# LPF_PA.net
KiCad netlist of a schematic drawn in Altium Designer
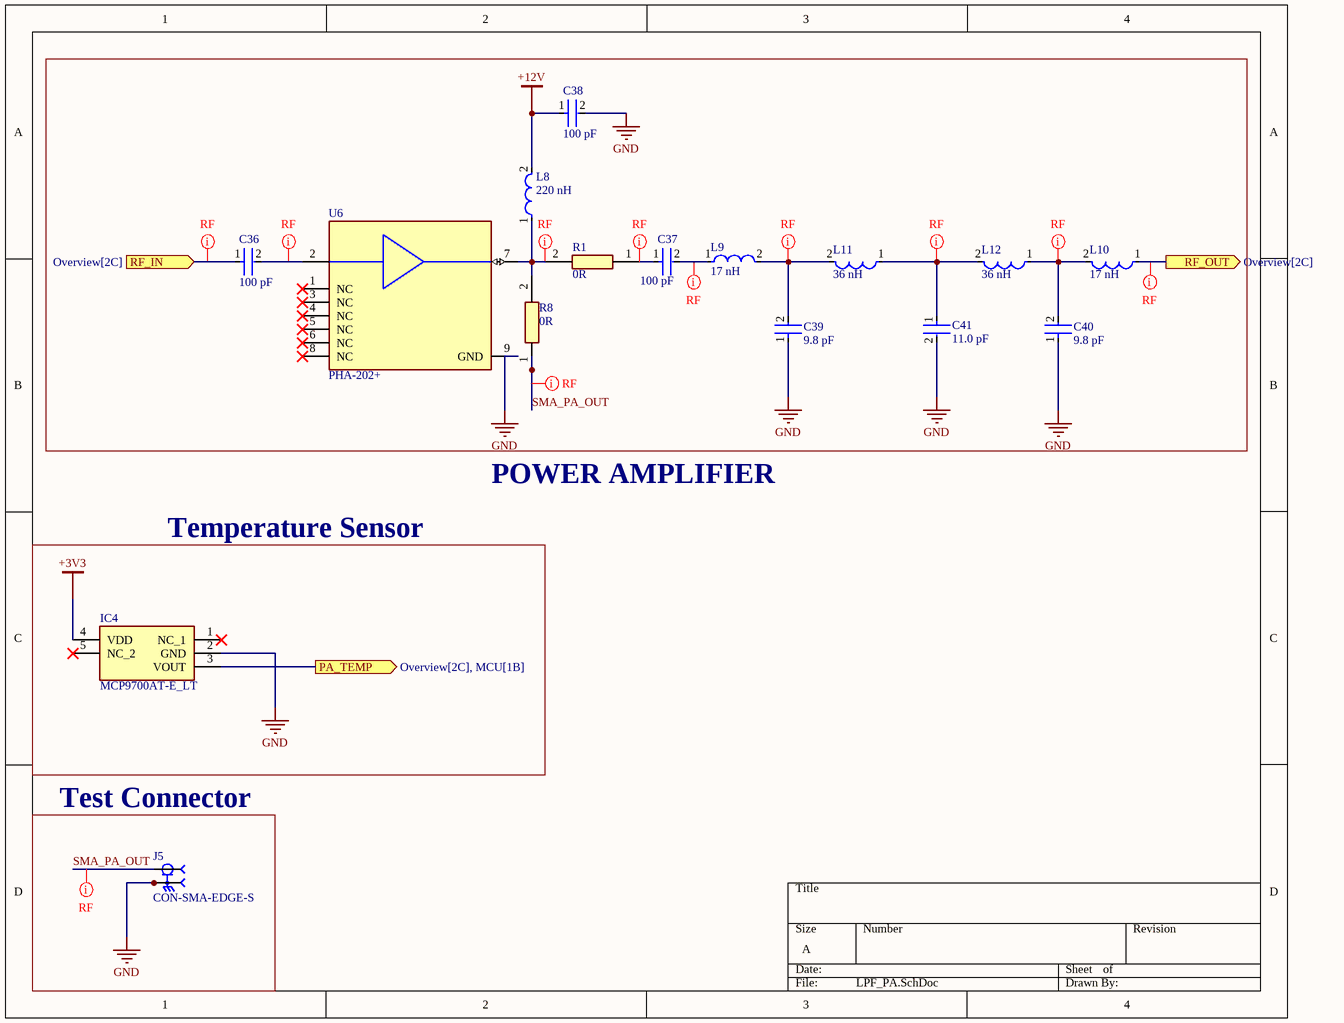
[diagram p0: LPF_PA.SchDoc]

(export (version "E")
  (design (tool "Eeschema 10.0.6"))
  (components
    (comp (ref "C36")
      (value "100 pF")
      (footprint "FP-GQM187-0_15-MFG")
      (description "Ceramic Capacitor 100pF ±5% 250VDC C0G 0603 Paper T/R Name: GQM1875C2E101JB12D")
      (fields (field (name "TOLERANCE") "5%"))
      (libsource (lib "Altium Content Vault") (part "02cd4be3c70576c341d710602a673aa"))
    )
    (comp (ref "C37")
      (value "100 pF")
      (footprint "FP-GQM187-0_15-MFG")
      (description "Ceramic Capacitor 100pF ±5% 250VDC C0G 0603 Paper T/R Name: GQM1875C2E101JB12D")
      (fields (field (name "TOLERANCE") "5%"))
      (libsource (lib "Altium Content Vault") (part "02cd4be3c70576c341d710602a673aa"))
    )
    (comp (ref "C38")
      (value "100 pF")
      (footprint "FP-GQM187-0_15-MFG")
      (description "Ceramic Capacitor 100pF ±5% 250VDC C0G 0603 Paper T/R Name: GQM1875C2E101JB12D")
      (fields (field (name "TOLERANCE") "5%"))
      (libsource (lib "Altium Content Vault") (part "02cd4be3c70576c341d710602a673aa"))
    )
    (comp (ref "C39")
      (value "9.8 pF")
      (footprint "FP-GJM155-0_05-IPC_A")
      (description "Multi-Layer Ceramic Capacitor 9.8pF C0G  ±0.05pF 0402 Paper T/R Name: GJM1555C1H9R8WB01D")
      (libsource (lib "Altium Content Vault") (part "02cd4be3c70576c341d710602a673aa"))
    )
    (comp (ref "C40")
      (value "9.8 pF")
      (footprint "FP-GJM155-0_05-IPC_A")
      (description "Multi-Layer Ceramic Capacitor 9.8pF C0G  ±0.05pF 0402 Paper T/R Name: GJM1555C1H9R8WB01D")
      (libsource (lib "Altium Content Vault") (part "02cd4be3c70576c341d710602a673aa"))
    )
    (comp (ref "C41")
      (value "11.0 pF")
      (footprint "FP-GJM155-0_05-IPC_B")
      (description "Multi-Layer Ceramic Capacitor 11pF C0G  ±2% 0402 Paper T/R Name: GJM1555C1H110GB01D")
      (fields (field (name "TOLERANCE") "2%"))
      (libsource (lib "Altium Content Vault") (part "02cd4be3c70576c341d710602a673aa"))
    )
    (comp (ref "IC4")
      (value "MCP9700AT-E_LT")
      (footprint "SamacSys:SOT65P210X110-5N")
      (description "Integrated Circuit")
      (fields
        (field (name "MANUFACTURER_PART_NUMBER") "MCP9700AT-E/LT")
        (field (name "MOUSER PART NUMBER") "579-MCP9700AT-E/LT")
      )
      (libsource (lib "*") (part "MCP9700AT-E_LT"))
    )
    (comp (ref "J5")
      (value "CON-SMA-EDGE-S")
      (footprint "RFSOLUTIONS_CON-SMA-EDGE-S")
      (description "SMA Connector Jack, Female Socket - Board Edge, End Launch Solder")
      (fields (field (name "MF") "RF Solutions") (field (name "DIGI-KEY_PART_NUMBER") "CON-SMA-EDGE-S-ND"))
      (libsource (lib "Americas- Calgary to Space- Calgary University") (part "CON-SMA-EDGE-S"))
    )
    (comp (ref "L8")
      (value "220 nH")
      (footprint "FP-LQW18AN_80-MFG")
      (description "Wire Wound RF Inductor for Automotive 220nH ±5% 280mA 2.08Ω 0603 (1608) Name: LQW18ANR22J8ZD")
      (libsource (lib "Altium Content Vault") (part "725321dda6339637d4d059423bc1c3c"))
    )
    (comp (ref "L9")
      (value "17 nH")
      (footprint "FP-LQW18AN_80-MFG")
      (description "Wire Wound RF Inductor for Automotive 17nH ±2% 1400mA 0.075Ω 0603 (1608) Name: LQW18AN17NG8ZD")
      (libsource (lib "Altium Content Vault") (part "725321dda6339637d4d059423bc1c3c"))
    )
    (comp (ref "L10")
      (value "17 nH")
      (footprint "FP-LQW18AN_80-MFG")
      (description "Wire Wound RF Inductor for Automotive 17nH ±2% 1400mA 0.075Ω 0603 (1608) Name: LQW18AN17NG8ZD")
      (libsource (lib "Altium Content Vault") (part "725321dda6339637d4d059423bc1c3c"))
    )
    (comp (ref "L11")
      (value "36 nH")
      (footprint "FP-LQW18AN_80-MFG")
      (description "Wire Wound RF Inductor for Automotive 36nH ±5% 910mA 0.2Ω 0603 (1608) Name: LQW18AN36NJ8ZD")
      (libsource (lib "Altium Content Vault") (part "725321dda6339637d4d059423bc1c3c"))
    )
    (comp (ref "L12")
      (value "36 nH")
      (footprint "FP-LQW18AN_80-MFG")
      (description "Wire Wound RF Inductor for Automotive 36nH ±5% 910mA 0.2Ω 0603 (1608) Name: LQW18AN36NJ8ZD")
      (libsource (lib "Altium Content Vault") (part "725321dda6339637d4d059423bc1c3c"))
    )
    (comp (ref "R1")
      (value "0R")
      (footprint "SamacSys:RESC1608X55N")
      (description "RC0603JR-070RL")
      (fields (field (name "MOUSER PART NUMBER") "603-RC0603JR-070RL"))
      (libsource (lib "") (part "RC0603JR-070RL_1"))
    )
    (comp (ref "R8")
      (value "0R")
      (footprint "SamacSys:RESC1608X55N")
      (description "RC0603JR-070RL")
      (fields (field (name "MOUSER PART NUMBER") "603-RC0603JR-070RL"))
      (libsource (lib "*") (part "RC0603JR-070RL"))
    )
    (comp (ref "U6")
      (value "PHA-202+")
      (footprint "FP-DL1636-MFG")
      (description "Ultra High Dynamic Range Monolithic Amplifier")
      (fields
        (field (name "MANUFACTURER") "Mini-Circuits")
        (field (name "OCTOPART") "https://octopart.com/pha-202%2B-mini-circuits-107467474")
      )
      (libsource (lib "Altium Content Vault") (part "dc888fa33c990a84ca3dff72230b88d"))
    )
  )
  (nets
    (net (code "1") (name "+3V3") (class "Default")
      (node (ref "IC4") (pin "4") (pinfunction "VDD_4") (pintype "passive"))
    )
    (net (code "2") (name "+12V") (class "Default")
      (node (ref "C38") (pin "1") (pinfunction "1_1") (pintype "passive"))
      (node (ref "L8") (pin "2") (pinfunction "2_2") (pintype "passive"))
    )
    (net (code "3") (name "/PA_TEMP") (class "Default")
      (node (ref "IC4") (pin "3") (pinfunction "VOUT_3") (pintype "passive"))
    )
    (net (code "4") (name "/RF_IN") (class "Default")
      (node (ref "C36") (pin "1") (pinfunction "1_1") (pintype "passive"))
    )
    (net (code "5") (name "/RF_OUT") (class "Default")
      (node (ref "L10") (pin "1") (pinfunction "1_1") (pintype "passive"))
    )
    (net (code "6") (name "/SMA_PA_OUT") (class "Default")
      (node (ref "J5") (pin "1") (pinfunction "1_1") (pintype "passive"))
      (node (ref "R8") (pin "1") (pinfunction "1_1") (pintype "passive"))
    )
    (net (code "7") (name "GND") (class "Default")
      (node (ref "C38") (pin "2") (pinfunction "2_2") (pintype "passive"))
      (node (ref "C39") (pin "1") (pinfunction "1_1") (pintype "passive"))
      (node (ref "C40") (pin "1") (pinfunction "1_1") (pintype "passive"))
      (node (ref "C41") (pin "2") (pinfunction "2_2") (pintype "passive"))
      (node (ref "IC4") (pin "2") (pinfunction "GND_2") (pintype "passive"))
      (node (ref "J5") (pin "G1") (pinfunction "2_G1") (pintype "passive"))
      (node (ref "J5") (pin "G2") (pinfunction "2_G2") (pintype "passive"))
      (node (ref "J5") (pin "G3") (pinfunction "2_G3") (pintype "passive"))
      (node (ref "J5") (pin "G4") (pinfunction "2_G4") (pintype "passive"))
      (node (ref "U6") (pin "9") (pinfunction "GND_9") (pintype "power_in"))
    )
    (net (code "8") (name "Net-(C37-Pad1)") (class "Default")
      (node (ref "C37") (pin "1") (pinfunction "1_1") (pintype "passive"))
      (node (ref "R1") (pin "1") (pinfunction "1_1") (pintype "passive"))
    )
    (net (code "9") (name "Net-(C37-Pad2)") (class "Default")
      (node (ref "C37") (pin "2") (pinfunction "2_2") (pintype "passive"))
      (node (ref "L9") (pin "1") (pinfunction "1_1") (pintype "passive"))
    )
    (net (code "10") (name "Net-(C39-Pad2)") (class "Default")
      (node (ref "C39") (pin "2") (pinfunction "2_2") (pintype "passive"))
      (node (ref "L11") (pin "2") (pinfunction "2_2") (pintype "passive"))
      (node (ref "L9") (pin "2") (pinfunction "2_2") (pintype "passive"))
    )
    (net (code "11") (name "Net-(C40-Pad2)") (class "Default")
      (node (ref "C40") (pin "2") (pinfunction "2_2") (pintype "passive"))
      (node (ref "L10") (pin "2") (pinfunction "2_2") (pintype "passive"))
      (node (ref "L12") (pin "1") (pinfunction "1_1") (pintype "passive"))
    )
    (net (code "12") (name "Net-(C41-Pad1)") (class "Default")
      (node (ref "C41") (pin "1") (pinfunction "1_1") (pintype "passive"))
      (node (ref "L11") (pin "1") (pinfunction "1_1") (pintype "passive"))
      (node (ref "L12") (pin "2") (pinfunction "2_2") (pintype "passive"))
    )
    (net (code "13") (name "Net-(U6-RF-IN)") (class "Default")
      (node (ref "C36") (pin "2") (pinfunction "2_2") (pintype "passive"))
      (node (ref "U6") (pin "2") (pinfunction "RF-IN_2") (pintype "passive"))
    )
    (net (code "14") (name "Net-(U6-RF-OUT&DC-IN)") (class "Default")
      (node (ref "L8") (pin "1") (pinfunction "1_1") (pintype "passive"))
      (node (ref "R1") (pin "2") (pinfunction "2_2") (pintype "passive"))
      (node (ref "R8") (pin "2") (pinfunction "2_2") (pintype "passive"))
      (node (ref "U6") (pin "7") (pinfunction "RF-OUT&DC-IN_7") (pintype "bidirectional"))
    )
    (net (code "15") (name "unconnected-(IC4-NC_1-Pad1)") (class "Default")
      (node (ref "IC4") (pin "1") (pinfunction "NC_1_1") (pintype "passive+no_connect"))
    )
    (net (code "16") (name "unconnected-(IC4-NC_2-Pad5)") (class "Default")
      (node (ref "IC4") (pin "5") (pinfunction "NC_2_5") (pintype "passive+no_connect"))
    )
    (net (code "17") (name "unconnected-(U6-NC-Pad1)") (class "Default")
      (node (ref "U6") (pin "1") (pinfunction "NC_1") (pintype "power_in+no_connect"))
    )
    (net (code "18") (name "unconnected-(U6-NC-Pad3)") (class "Default")
      (node (ref "U6") (pin "3") (pinfunction "NC_3") (pintype "passive+no_connect"))
    )
    (net (code "19") (name "unconnected-(U6-NC-Pad4)") (class "Default")
      (node (ref "U6") (pin "4") (pinfunction "NC_4") (pintype "passive+no_connect"))
    )
    (net (code "20") (name "unconnected-(U6-NC-Pad5)") (class "Default")
      (node (ref "U6") (pin "5") (pinfunction "NC_5") (pintype "passive+no_connect"))
    )
    (net (code "21") (name "unconnected-(U6-NC-Pad6)") (class "Default")
      (node (ref "U6") (pin "6") (pinfunction "NC_6") (pintype "passive+no_connect"))
    )
    (net (code "22") (name "unconnected-(U6-NC-Pad8)") (class "Default")
      (node (ref "U6") (pin "8") (pinfunction "NC_8") (pintype "passive+no_connect"))
    )
  )
)
